# me433Schematic.net
KiCad netlist of a schematic drawn in EAGLE
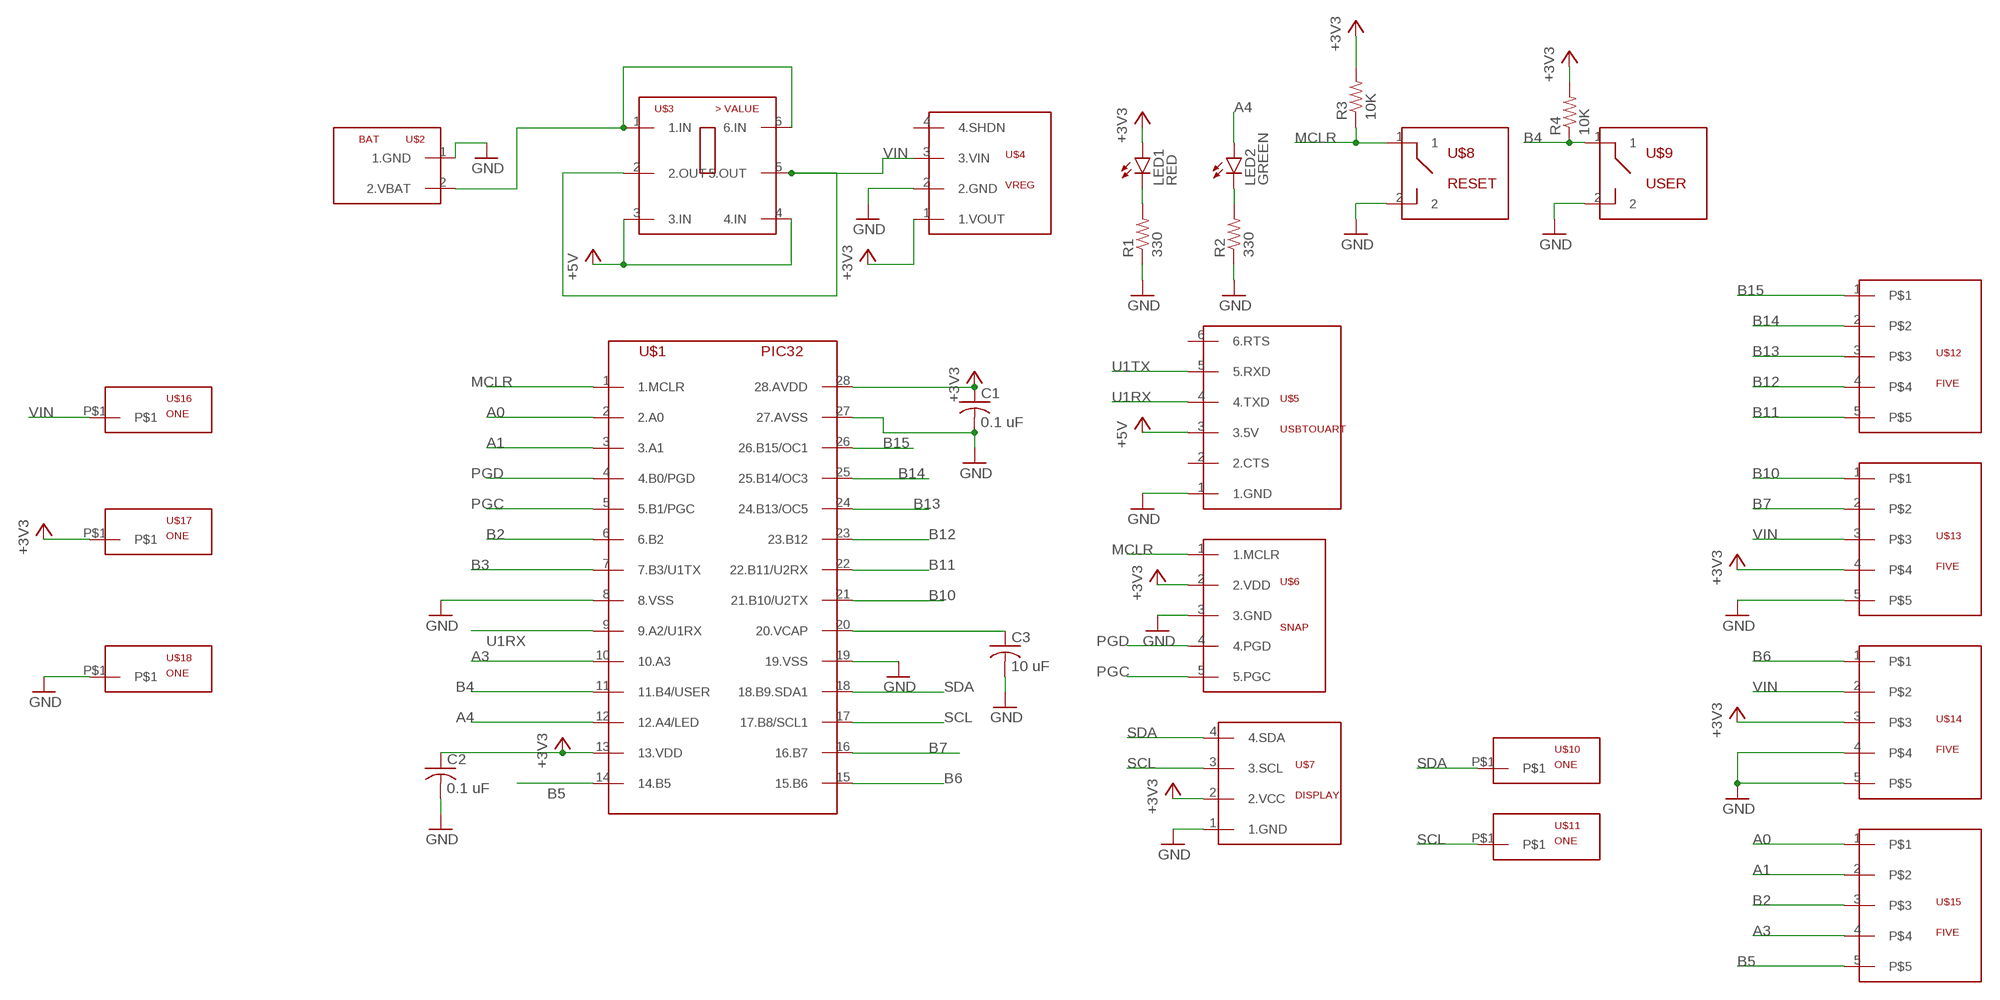
[diagram p0: schematic, sheet 1]

(export (version "E")
  (design (tool "Eeschema 10.0.6"))
  (components
    (comp (ref "C1")
      (value "0.1 uF")
      (footprint "eagle-import:C025-024X044")
      (libsource (lib "eagle-import") (part "C-US025-024X044"))
    )
    (comp (ref "C2")
      (value "0.1 uF")
      (footprint "eagle-import:C025-024X044")
      (libsource (lib "eagle-import") (part "C-US025-024X044"))
    )
    (comp (ref "C3")
      (value "10 uF")
      (footprint "eagle-import:C025-024X044")
      (libsource (lib "eagle-import") (part "C-US025-024X044"))
    )
    (comp (ref "LED1")
      (value "RED")
      (footprint "eagle-import:LED3MM")
      (libsource (lib "eagle-import") (part "LED3MM"))
    )
    (comp (ref "LED2")
      (value "GREEN")
      (footprint "eagle-import:LED3MM")
      (libsource (lib "eagle-import") (part "LED3MM"))
    )
    (comp (ref "R1")
      (value "330")
      (footprint "eagle-import:0207_7")
      (libsource (lib "eagle-import") (part "R-US_0207/7"))
    )
    (comp (ref "R2")
      (value "330")
      (footprint "eagle-import:0207_7")
      (libsource (lib "eagle-import") (part "R-US_0207/7"))
    )
    (comp (ref "R3")
      (value "10K")
      (footprint "eagle-import:0207_7")
      (libsource (lib "eagle-import") (part "R-US_0207/7"))
    )
    (comp (ref "R4")
      (value "10K")
      (footprint "eagle-import:0207_7")
      (libsource (lib "eagle-import") (part "R-US_0207/7"))
    )
    (comp (ref "U$1")
      (value "PIC32")
      (footprint "eagle-import:DIL28-3")
      (libsource (lib "eagle-import") (part "PIC32"))
    )
    (comp (ref "U$2")
      (value "BAT")
      (footprint "eagle-import:BAT")
      (libsource (lib "eagle-import") (part "BAT"))
    )
    (comp (ref "U$3")
      (value "SLIDE")
      (footprint "eagle-import:SLIDE")
      (libsource (lib "eagle-import") (part "SLIDE"))
    )
    (comp (ref "U$4")
      (value "VREG")
      (footprint "eagle-import:VREG")
      (libsource (lib "eagle-import") (part "VREG"))
    )
    (comp (ref "U$5")
      (value "USBTOUART")
      (footprint "eagle-import:USBTOUART")
      (libsource (lib "eagle-import") (part "USBTOUART"))
    )
    (comp (ref "U$6")
      (value "SNAP")
      (footprint "eagle-import:SNAP")
      (libsource (lib "eagle-import") (part "SNAP"))
    )
    (comp (ref "U$7")
      (value "DISPLAY")
      (footprint "eagle-import:DISPLAY")
      (libsource (lib "eagle-import") (part "DISPLAY"))
    )
    (comp (ref "U$8")
      (value "RESET")
      (footprint "eagle-import:BUTTON")
      (libsource (lib "eagle-import") (part "BUTTON"))
    )
    (comp (ref "U$9")
      (value "USER")
      (footprint "eagle-import:BUTTON")
      (libsource (lib "eagle-import") (part "BUTTON"))
    )
    (comp (ref "U$10")
      (value "ONE")
      (footprint "eagle-import:ONE")
      (libsource (lib "eagle-import") (part "ONE"))
    )
    (comp (ref "U$11")
      (value "ONE")
      (footprint "eagle-import:ONE")
      (libsource (lib "eagle-import") (part "ONE"))
    )
    (comp (ref "U$12")
      (value "FIVE")
      (footprint "eagle-import:FIVE")
      (libsource (lib "eagle-import") (part "FIVE"))
    )
    (comp (ref "U$13")
      (value "FIVE")
      (footprint "eagle-import:FIVE")
      (libsource (lib "eagle-import") (part "FIVE"))
    )
    (comp (ref "U$14")
      (value "FIVE")
      (footprint "eagle-import:FIVE")
      (libsource (lib "eagle-import") (part "FIVE"))
    )
    (comp (ref "U$15")
      (value "FIVE")
      (footprint "eagle-import:FIVE")
      (libsource (lib "eagle-import") (part "FIVE"))
    )
    (comp (ref "U$16")
      (value "ONE")
      (footprint "eagle-import:ONE")
      (libsource (lib "eagle-import") (part "ONE"))
    )
    (comp (ref "U$17")
      (value "ONE")
      (footprint "eagle-import:ONE")
      (libsource (lib "eagle-import") (part "ONE"))
    )
    (comp (ref "U$18")
      (value "ONE")
      (footprint "eagle-import:ONE")
      (libsource (lib "eagle-import") (part "ONE"))
    )
  )
  (nets
    (net (code "1") (name "+3V3") (class "Default")
      (node (ref "C1") (pin "1") (pinfunction "1_1") (pintype "passive"))
      (node (ref "C2") (pin "1") (pinfunction "1_1") (pintype "passive"))
      (node (ref "LED1") (pin "A") (pinfunction "A_A") (pintype "passive"))
      (node (ref "R3") (pin "2") (pinfunction "2_2") (pintype "passive"))
      (node (ref "R4") (pin "2") (pinfunction "2_2") (pintype "passive"))
      (node (ref "U$1") (pin "13") (pinfunction "13.VDD_13") (pintype "bidirectional"))
      (node (ref "U$1") (pin "28") (pinfunction "28.AVDD_28") (pintype "bidirectional"))
      (node (ref "U$13") (pin "4") (pinfunction "P$4_4") (pintype "bidirectional"))
      (node (ref "U$14") (pin "3") (pinfunction "P$3_3") (pintype "bidirectional"))
      (node (ref "U$17") (pin "P$1") (pinfunction "P$1_P$1") (pintype "bidirectional"))
      (node (ref "U$4") (pin "1") (pinfunction "1.VOUT_1") (pintype "bidirectional"))
      (node (ref "U$6") (pin "2") (pinfunction "2.VDD_2") (pintype "bidirectional"))
      (node (ref "U$7") (pin "2.") (pinfunction "2.VCC_2.") (pintype "bidirectional"))
    )
    (net (code "2") (name "+5V") (class "Default")
      (node (ref "U$3") (pin "3") (pinfunction "3.IN_3") (pintype "bidirectional"))
      (node (ref "U$3") (pin "4") (pinfunction "4.IN_4") (pintype "bidirectional"))
      (node (ref "U$5") (pin "3") (pinfunction "3.5V_3") (pintype "bidirectional"))
    )
    (net (code "3") (name "/A0") (class "Default")
      (node (ref "U$1") (pin "2") (pinfunction "2.A0_2") (pintype "bidirectional"))
      (node (ref "U$15") (pin "1") (pinfunction "P$1_1") (pintype "bidirectional"))
    )
    (net (code "4") (name "/A1") (class "Default")
      (node (ref "U$1") (pin "3") (pinfunction "3.A1_3") (pintype "bidirectional"))
      (node (ref "U$15") (pin "2") (pinfunction "P$2_2") (pintype "bidirectional"))
    )
    (net (code "5") (name "/A3") (class "Default")
      (node (ref "U$1") (pin "10") (pinfunction "10.A3_10") (pintype "bidirectional"))
      (node (ref "U$15") (pin "4") (pinfunction "P$4_4") (pintype "bidirectional"))
    )
    (net (code "6") (name "/A4") (class "Default")
      (node (ref "LED2") (pin "A") (pinfunction "A_A") (pintype "passive"))
      (node (ref "U$1") (pin "12") (pinfunction "12.A4/LED_12") (pintype "bidirectional"))
    )
    (net (code "7") (name "/B2") (class "Default")
      (node (ref "U$1") (pin "6") (pinfunction "6.B2_6") (pintype "bidirectional"))
      (node (ref "U$15") (pin "3") (pinfunction "P$3_3") (pintype "bidirectional"))
    )
    (net (code "8") (name "/B3") (class "Default")
      (node (ref "U$1") (pin "7") (pinfunction "7.B3/U1TX_7") (pintype "bidirectional"))
    )
    (net (code "9") (name "/B4") (class "Default")
      (node (ref "R4") (pin "1") (pinfunction "1_1") (pintype "passive"))
      (node (ref "U$1") (pin "11") (pinfunction "11.B4/USER_11") (pintype "bidirectional"))
      (node (ref "U$9") (pin "1") (pinfunction "1_1") (pintype "bidirectional"))
    )
    (net (code "10") (name "/B5") (class "Default")
      (node (ref "U$1") (pin "14") (pinfunction "14.B5_14") (pintype "bidirectional"))
      (node (ref "U$15") (pin "5") (pinfunction "P$5_5") (pintype "bidirectional"))
    )
    (net (code "11") (name "/B6") (class "Default")
      (node (ref "U$1") (pin "15") (pinfunction "15.B6_15") (pintype "bidirectional"))
      (node (ref "U$14") (pin "1") (pinfunction "P$1_1") (pintype "bidirectional"))
    )
    (net (code "12") (name "/B7") (class "Default")
      (node (ref "U$1") (pin "16") (pinfunction "16.B7_16") (pintype "bidirectional"))
      (node (ref "U$13") (pin "2") (pinfunction "P$2_2") (pintype "bidirectional"))
    )
    (net (code "13") (name "/B10") (class "Default")
      (node (ref "U$1") (pin "21") (pinfunction "21.B10/U2TX_21") (pintype "bidirectional"))
      (node (ref "U$13") (pin "1") (pinfunction "P$1_1") (pintype "bidirectional"))
    )
    (net (code "14") (name "/B11") (class "Default")
      (node (ref "U$1") (pin "22") (pinfunction "22.B11/U2RX_22") (pintype "bidirectional"))
      (node (ref "U$12") (pin "5") (pinfunction "P$5_5") (pintype "bidirectional"))
    )
    (net (code "15") (name "/B12") (class "Default")
      (node (ref "U$1") (pin "23") (pinfunction "23.B12_23") (pintype "bidirectional"))
      (node (ref "U$12") (pin "4") (pinfunction "P$4_4") (pintype "bidirectional"))
    )
    (net (code "16") (name "/B13") (class "Default")
      (node (ref "U$1") (pin "24") (pinfunction "24.B13/OC5_24") (pintype "bidirectional"))
      (node (ref "U$12") (pin "3") (pinfunction "P$3_3") (pintype "bidirectional"))
    )
    (net (code "17") (name "/B14") (class "Default")
      (node (ref "U$1") (pin "25") (pinfunction "25.B14/OC3_25") (pintype "bidirectional"))
      (node (ref "U$12") (pin "2") (pinfunction "P$2_2") (pintype "bidirectional"))
    )
    (net (code "18") (name "/B15") (class "Default")
      (node (ref "U$1") (pin "26") (pinfunction "26.B15/OC1_26") (pintype "bidirectional"))
      (node (ref "U$12") (pin "1") (pinfunction "P$1_1") (pintype "bidirectional"))
    )
    (net (code "19") (name "/MCLR") (class "Default")
      (node (ref "R3") (pin "1") (pinfunction "1_1") (pintype "passive"))
      (node (ref "U$1") (pin "1") (pinfunction "1.MCLR_1") (pintype "bidirectional"))
      (node (ref "U$6") (pin "1") (pinfunction "1.MCLR_1") (pintype "bidirectional"))
      (node (ref "U$8") (pin "1") (pinfunction "1_1") (pintype "bidirectional"))
    )
    (net (code "20") (name "/PGC") (class "Default")
      (node (ref "U$1") (pin "5") (pinfunction "5.B1/PGC_5") (pintype "bidirectional"))
      (node (ref "U$6") (pin "5") (pinfunction "5.PGC_5") (pintype "bidirectional"))
    )
    (net (code "21") (name "/PGD") (class "Default")
      (node (ref "U$1") (pin "4") (pinfunction "4.B0/PGD_4") (pintype "bidirectional"))
      (node (ref "U$6") (pin "4") (pinfunction "4.PGD_4") (pintype "bidirectional"))
    )
    (net (code "22") (name "/SCL") (class "Default")
      (node (ref "U$1") (pin "17") (pinfunction "17.B8/SCL1_17") (pintype "bidirectional"))
      (node (ref "U$11") (pin "P$1") (pinfunction "P$1_P$1") (pintype "bidirectional"))
      (node (ref "U$7") (pin "3.") (pinfunction "3.SCL_3.") (pintype "bidirectional"))
    )
    (net (code "23") (name "/SDA") (class "Default")
      (node (ref "U$1") (pin "18") (pinfunction "18.B9.SDA1_18") (pintype "bidirectional"))
      (node (ref "U$10") (pin "P$1") (pinfunction "P$1_P$1") (pintype "bidirectional"))
      (node (ref "U$7") (pin "4.") (pinfunction "4.SDA_4.") (pintype "bidirectional"))
    )
    (net (code "24") (name "/U1RX") (class "Default")
      (node (ref "U$1") (pin "9") (pinfunction "9.A2/U1RX_9") (pintype "bidirectional"))
      (node (ref "U$5") (pin "4") (pinfunction "4.TXD_4") (pintype "bidirectional"))
    )
    (net (code "25") (name "/U1TX") (class "Default")
      (node (ref "U$5") (pin "5") (pinfunction "5.RXD_5") (pintype "bidirectional"))
    )
    (net (code "26") (name "/VIN") (class "Default")
      (node (ref "U$13") (pin "3") (pinfunction "P$3_3") (pintype "bidirectional"))
      (node (ref "U$14") (pin "2") (pinfunction "P$2_2") (pintype "bidirectional"))
      (node (ref "U$16") (pin "P$1") (pinfunction "P$1_P$1") (pintype "bidirectional"))
      (node (ref "U$3") (pin "2") (pinfunction "2.OUT_2") (pintype "bidirectional"))
      (node (ref "U$3") (pin "5") (pinfunction "5.OUT_5") (pintype "bidirectional"))
      (node (ref "U$4") (pin "3") (pinfunction "3.VIN_3") (pintype "bidirectional"))
    )
    (net (code "27") (name "GND") (class "Default")
      (node (ref "C1") (pin "2") (pinfunction "2_2") (pintype "passive"))
      (node (ref "C2") (pin "2") (pinfunction "2_2") (pintype "passive"))
      (node (ref "C3") (pin "2") (pinfunction "2_2") (pintype "passive"))
      (node (ref "R1") (pin "1") (pinfunction "1_1") (pintype "passive"))
      (node (ref "R2") (pin "1") (pinfunction "1_1") (pintype "passive"))
      (node (ref "U$1") (pin "19") (pinfunction "19.VSS_19") (pintype "bidirectional"))
      (node (ref "U$1") (pin "27") (pinfunction "27.AVSS_27") (pintype "bidirectional"))
      (node (ref "U$1") (pin "8") (pinfunction "8.VSS_8") (pintype "bidirectional"))
      (node (ref "U$13") (pin "5") (pinfunction "P$5_5") (pintype "bidirectional"))
      (node (ref "U$14") (pin "4") (pinfunction "P$4_4") (pintype "bidirectional"))
      (node (ref "U$14") (pin "5") (pinfunction "P$5_5") (pintype "bidirectional"))
      (node (ref "U$18") (pin "P$1") (pinfunction "P$1_P$1") (pintype "bidirectional"))
      (node (ref "U$2") (pin "1") (pinfunction "1.GND_1") (pintype "bidirectional"))
      (node (ref "U$4") (pin "2") (pinfunction "2.GND_2") (pintype "bidirectional"))
      (node (ref "U$5") (pin "1") (pinfunction "1.GND_1") (pintype "bidirectional"))
      (node (ref "U$6") (pin "3") (pinfunction "3.GND_3") (pintype "bidirectional"))
      (node (ref "U$7") (pin "1.") (pinfunction "1.GND_1.") (pintype "bidirectional"))
      (node (ref "U$8") (pin "2") (pinfunction "2_2") (pintype "bidirectional"))
      (node (ref "U$9") (pin "2") (pinfunction "2_2") (pintype "bidirectional"))
    )
    (net (code "28") (name "Net-(LED1-C)") (class "Default")
      (node (ref "LED1") (pin "K") (pinfunction "C_K") (pintype "passive"))
      (node (ref "R1") (pin "2") (pinfunction "2_2") (pintype "passive"))
    )
    (net (code "29") (name "Net-(LED2-C)") (class "Default")
      (node (ref "LED2") (pin "K") (pinfunction "C_K") (pintype "passive"))
      (node (ref "R2") (pin "2") (pinfunction "2_2") (pintype "passive"))
    )
    (net (code "30") (name "Net-(U$1-20.VCAP)") (class "Default")
      (node (ref "C3") (pin "1") (pinfunction "1_1") (pintype "passive"))
      (node (ref "U$1") (pin "20") (pinfunction "20.VCAP_20") (pintype "bidirectional"))
    )
    (net (code "31") (name "Net-(U$2-2.VBAT)") (class "Default")
      (node (ref "U$2") (pin "2") (pinfunction "2.VBAT_2") (pintype "bidirectional"))
      (node (ref "U$3") (pin "1") (pinfunction "1.IN_1") (pintype "bidirectional"))
      (node (ref "U$3") (pin "6") (pinfunction "6.IN_6") (pintype "bidirectional"))
    )
    (net (code "32") (name "unconnected-(U$4-4.SHDN-Pad4)") (class "Default")
      (node (ref "U$4") (pin "4") (pinfunction "4.SHDN_4") (pintype "bidirectional"))
    )
    (net (code "33") (name "unconnected-(U$5-2.CTS-Pad2)") (class "Default")
      (node (ref "U$5") (pin "2") (pinfunction "2.CTS_2") (pintype "bidirectional"))
    )
    (net (code "34") (name "unconnected-(U$5-6.RTS-Pad6)") (class "Default")
      (node (ref "U$5") (pin "6") (pinfunction "6.RTS_6") (pintype "bidirectional"))
    )
  )
)
